# Sheet10.net
KiCad netlist of a schematic drawn in Altium Designer
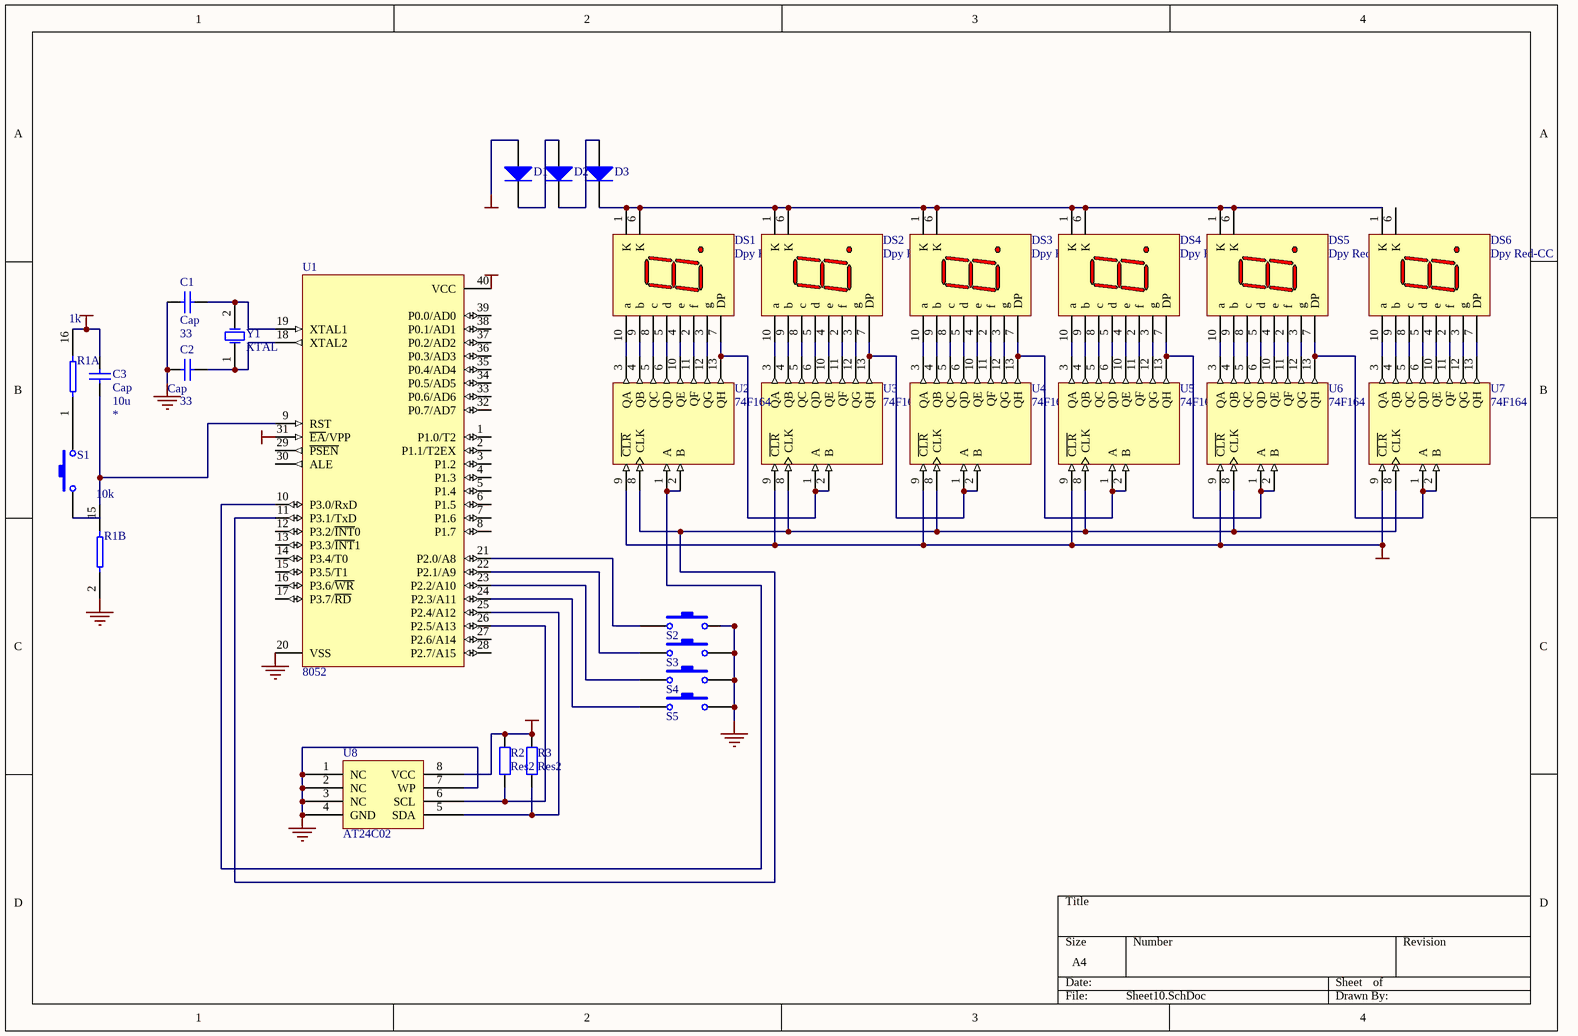
[diagram p0: Sheet10.SchDoc]

(export (version "E")
  (design (tool "Eeschema 10.0.6"))
  (components
    (comp (ref "C1")
      (value "Cap")
      (footprint "RAD-0.3")
      (description "Capacitor")
      (fields (field (name "ALTIUM_UNNAMED_1") "33") (field (name "PUBLISHER") "Altium Limited"))
      (libsource (lib "Miscellaneous Devices") (part "Cap"))
    )
    (comp (ref "C2")
      (value "Cap")
      (footprint "RAD-0.3")
      (description "Capacitor")
      (fields (field (name "ALTIUM_UNNAMED_1") "33") (field (name "PUBLISHER") "Altium Limited"))
      (libsource (lib "Miscellaneous Devices") (part "Cap"))
    )
    (comp (ref "C3")
      (value "Cap")
      (footprint "RAD-0.3")
      (description "Capacitor")
      (fields
        (field (name "ALTIUM_UNNAMED_1") "10u")
        (field (name "ALTIUM_UNNAMED_2") "*")
        (field (name "PUBLISHER") "Altium Limited")
      )
      (libsource (lib "Miscellaneous Devices") (part "Cap"))
    )
    (comp (ref "D1")
      (value "Diode BAS21")
      (footprint "SO-G3/C2.5")
      (description "Silicon Switching Diode for High-Speed, High-Voltage Switching")
      (fields (field (name "PUBLISHER") "Altium Limited"))
      (libsource (lib "Miscellaneous Devices") (part "Diode BAS21"))
    )
    (comp (ref "D2")
      (value "Diode BAS21")
      (footprint "SO-G3/C2.5")
      (description "Silicon Switching Diode for High-Speed, High-Voltage Switching")
      (fields (field (name "PUBLISHER") "Altium Limited"))
      (libsource (lib "Miscellaneous Devices") (part "Diode BAS21"))
    )
    (comp (ref "D3")
      (value "Diode BAS21")
      (footprint "SO-G3/C2.5")
      (description "Silicon Switching Diode for High-Speed, High-Voltage Switching")
      (fields (field (name "PUBLISHER") "Altium Limited"))
      (libsource (lib "Miscellaneous Devices") (part "Diode BAS21"))
    )
    (comp (ref "DS1")
      (value "Dpy Red-CC")
      (footprint "LEDDIP-10/C5.08RHD")
      (description "7.62 mm Black Surface HER 7-Segment Display: CC, RH DP")
      (fields (field (name "PUBLISHER") "Altium Limited"))
      (libsource (lib "Miscellaneous Devices") (part "Dpy Red-CC"))
    )
    (comp (ref "DS2")
      (value "Dpy Red-CC")
      (footprint "LEDDIP-10/C5.08RHD")
      (description "7.62 mm Black Surface HER 7-Segment Display: CC, RH DP")
      (fields (field (name "PUBLISHER") "Altium Limited"))
      (libsource (lib "Miscellaneous Devices") (part "Dpy Red-CC"))
    )
    (comp (ref "DS3")
      (value "Dpy Red-CC")
      (footprint "LEDDIP-10/C5.08RHD")
      (description "7.62 mm Black Surface HER 7-Segment Display: CC, RH DP")
      (fields (field (name "PUBLISHER") "Altium Limited"))
      (libsource (lib "Miscellaneous Devices") (part "Dpy Red-CC"))
    )
    (comp (ref "DS4")
      (value "Dpy Red-CC")
      (footprint "LEDDIP-10/C5.08RHD")
      (description "7.62 mm Black Surface HER 7-Segment Display: CC, RH DP")
      (fields (field (name "PUBLISHER") "Altium Limited"))
      (libsource (lib "Miscellaneous Devices") (part "Dpy Red-CC"))
    )
    (comp (ref "DS5")
      (value "Dpy Red-CC")
      (footprint "LEDDIP-10/C5.08RHD")
      (description "7.62 mm Black Surface HER 7-Segment Display: CC, RH DP")
      (fields (field (name "PUBLISHER") "Altium Limited"))
      (libsource (lib "Miscellaneous Devices") (part "Dpy Red-CC"))
    )
    (comp (ref "DS6")
      (value "Dpy Red-CC")
      (footprint "LEDDIP-10/C5.08RHD")
      (description "7.62 mm Black Surface HER 7-Segment Display: CC, RH DP")
      (fields (field (name "PUBLISHER") "Altium Limited"))
      (libsource (lib "Miscellaneous Devices") (part "Dpy Red-CC"))
    )
    (comp (ref "R1")
      (value "Res Pack2")
      (footprint "DIP-16")
      (description "Isolated Resistor Network - Parts")
      (fields (field (name "ALTIUM_UNNAMED_1") "1k") (field (name "PUBLISHER") "Altium Limited"))
      (libsource (lib "Miscellaneous Devices") (part "Res Pack2"))
    )
    (comp (ref "R2")
      (value "Res2")
      (footprint "AXIAL-0.4")
      (description "Resistor")
      (fields (field (name "PUBLISHER") "Altium Limited"))
      (libsource (lib "Miscellaneous Devices") (part "Res2"))
    )
    (comp (ref "R3")
      (value "Res2")
      (footprint "AXIAL-0.4")
      (description "Resistor")
      (fields (field (name "PUBLISHER") "Altium Limited"))
      (libsource (lib "Miscellaneous Devices") (part "Res2"))
    )
    (comp (ref "S1")
      (value "SW-PB")
      (footprint "SPST-2")
      (description "Switch")
      (fields (field (name "PUBLISHER") "Altium Limited"))
      (libsource (lib "Miscellaneous Devices") (part "SW-PB"))
    )
    (comp (ref "S2")
      (value "SW-PB")
      (footprint "SPST-2")
      (description "Switch")
      (fields (field (name "PUBLISHER") "Altium Limited"))
      (libsource (lib "Miscellaneous Devices") (part "SW-PB"))
    )
    (comp (ref "S3")
      (value "SW-PB")
      (footprint "SPST-2")
      (description "Switch")
      (fields (field (name "PUBLISHER") "Altium Limited"))
      (libsource (lib "Miscellaneous Devices") (part "SW-PB"))
    )
    (comp (ref "S4")
      (value "SW-PB")
      (footprint "SPST-2")
      (description "Switch")
      (fields (field (name "PUBLISHER") "Altium Limited"))
      (libsource (lib "Miscellaneous Devices") (part "SW-PB"))
    )
    (comp (ref "S5")
      (value "SW-PB")
      (footprint "SPST-2")
      (description "Switch")
      (fields (field (name "PUBLISHER") "Altium Limited"))
      (libsource (lib "Miscellaneous Devices") (part "SW-PB"))
    )
    (comp (ref "U1")
      (value "8052")
      (footprint "SOT129-1")
      (description "80C51 8-Bit Microcontroller Family: 128 B RAM, ROMless, 2.7 V-5.5 V, Low Power, High Speed")
      (fields (field (name "PUBLISHER") "Altium Limited"))
      (libsource (lib "Philips Microcontroller 8-Bit") (part "P80C31SBPN"))
    )
    (comp (ref "U2")
      (value "74F164")
      (footprint "DIP-14")
      (description "8-Bit Parallel-Out Serial Shift Register")
      (libsource (lib "74xx") (part "74F164"))
    )
    (comp (ref "U3")
      (value "74F164")
      (footprint "DIP-14")
      (description "8-Bit Parallel-Out Serial Shift Register")
      (libsource (lib "74xx") (part "74F164"))
    )
    (comp (ref "U4")
      (value "74F164")
      (footprint "DIP-14")
      (description "8-Bit Parallel-Out Serial Shift Register")
      (libsource (lib "74xx") (part "74F164"))
    )
    (comp (ref "U5")
      (value "74F164")
      (footprint "DIP-14")
      (description "8-Bit Parallel-Out Serial Shift Register")
      (libsource (lib "74xx") (part "74F164"))
    )
    (comp (ref "U6")
      (value "74F164")
      (footprint "DIP-14")
      (description "8-Bit Parallel-Out Serial Shift Register")
      (libsource (lib "74xx") (part "74F164"))
    )
    (comp (ref "U7")
      (value "74F164")
      (footprint "DIP-14")
      (description "8-Bit Parallel-Out Serial Shift Register")
      (libsource (lib "74xx") (part "74F164"))
    )
    (comp (ref "U8") (value "AT24C02") (libsource (lib "AT24C02") (part "Component_")))
    (comp (ref "Y1")
      (value "XTAL")
      (footprint "BCY-W2/D3.1")
      (description "Crystal Oscillator")
      (fields (field (name "PUBLISHER") "Altium Limited"))
      (libsource (lib "Miscellaneous Devices") (part "XTAL"))
    )
  )
  (nets
    (net (code "1") (name "+5") (class "Default")
      (node (ref "D1") (pin "1") (pinfunction "A_1") (pintype "passive"))
      (node (ref "R2") (pin "2") (pinfunction "2_2") (pintype "passive"))
      (node (ref "R3") (pin "2") (pinfunction "2_2") (pintype "passive"))
      (node (ref "U1") (pin "31") (pinfunction "~{EA}/VPP_31") (pintype "input"))
      (node (ref "U1") (pin "40") (pinfunction "VCC_40") (pintype "power_in"))
      (node (ref "U8") (pin "8") (pinfunction "VCC_8") (pintype "passive"))
    )
    (net (code "2") (name "+5v") (class "Default")
      (node (ref "C3") (pin "2") (pinfunction "2_2") (pintype "passive"))
      (node (ref "R1") (pin "16") (pinfunction "16_16") (pintype "passive"))
    )
    (net (code "3") (name "GND") (class "Default")
      (node (ref "C1") (pin "2") (pinfunction "2_2") (pintype "passive"))
      (node (ref "C2") (pin "2") (pinfunction "2_2") (pintype "passive"))
      (node (ref "R1") (pin "2") (pinfunction "2_2") (pintype "passive"))
      (node (ref "S2") (pin "2") (pinfunction "2_2") (pintype "passive"))
      (node (ref "S3") (pin "2") (pinfunction "2_2") (pintype "passive"))
      (node (ref "S4") (pin "2") (pinfunction "2_2") (pintype "passive"))
      (node (ref "S5") (pin "2") (pinfunction "2_2") (pintype "passive"))
      (node (ref "U1") (pin "20") (pinfunction "VSS_20") (pintype "power_in"))
      (node (ref "U2") (pin "7") (pinfunction "GND_7") (pintype "power_in"))
      (node (ref "U3") (pin "7") (pinfunction "GND_7") (pintype "power_in"))
      (node (ref "U4") (pin "7") (pinfunction "GND_7") (pintype "power_in"))
      (node (ref "U5") (pin "7") (pinfunction "GND_7") (pintype "power_in"))
      (node (ref "U6") (pin "7") (pinfunction "GND_7") (pintype "power_in"))
      (node (ref "U7") (pin "7") (pinfunction "GND_7") (pintype "power_in"))
      (node (ref "U8") (pin "1") (pinfunction "NC_1") (pintype "passive"))
      (node (ref "U8") (pin "2") (pinfunction "NC_2") (pintype "passive"))
      (node (ref "U8") (pin "3") (pinfunction "NC_3") (pintype "passive"))
      (node (ref "U8") (pin "4") (pinfunction "GND_4") (pintype "passive"))
      (node (ref "U8") (pin "7") (pinfunction "WP_7") (pintype "passive"))
    )
    (net (code "4") (name "Net-(D1-K)") (class "Default")
      (node (ref "D1") (pin "3") (pinfunction "K_3") (pintype "passive"))
      (node (ref "D2") (pin "1") (pinfunction "A_1") (pintype "passive"))
    )
    (net (code "5") (name "Net-(D2-K)") (class "Default")
      (node (ref "D2") (pin "3") (pinfunction "K_3") (pintype "passive"))
      (node (ref "D3") (pin "1") (pinfunction "A_1") (pintype "passive"))
    )
    (net (code "6") (name "Net-(D3-K)") (class "Default")
      (node (ref "D3") (pin "3") (pinfunction "K_3") (pintype "passive"))
      (node (ref "DS1") (pin "1") (pinfunction "K_1") (pintype "passive"))
      (node (ref "DS1") (pin "6") (pinfunction "K_6") (pintype "passive"))
      (node (ref "DS2") (pin "1") (pinfunction "K_1") (pintype "passive"))
      (node (ref "DS2") (pin "6") (pinfunction "K_6") (pintype "passive"))
      (node (ref "DS3") (pin "1") (pinfunction "K_1") (pintype "passive"))
      (node (ref "DS3") (pin "6") (pinfunction "K_6") (pintype "passive"))
      (node (ref "DS4") (pin "1") (pinfunction "K_1") (pintype "passive"))
      (node (ref "DS4") (pin "6") (pinfunction "K_6") (pintype "passive"))
      (node (ref "DS5") (pin "1") (pinfunction "K_1") (pintype "passive"))
      (node (ref "DS5") (pin "6") (pinfunction "K_6") (pintype "passive"))
      (node (ref "DS6") (pin "1") (pinfunction "K_1") (pintype "passive"))
    )
    (net (code "7") (name "Net-(DS1-DP)") (class "Default")
      (node (ref "DS1") (pin "7") (pinfunction "DP_7") (pintype "passive"))
      (node (ref "U2") (pin "13") (pinfunction "QH_13") (pintype "output"))
      (node (ref "U3") (pin "1") (pinfunction "A_1") (pintype "input"))
      (node (ref "U3") (pin "2") (pinfunction "B_2") (pintype "input"))
    )
    (net (code "8") (name "Net-(DS1-a)") (class "Default")
      (node (ref "DS1") (pin "10") (pinfunction "a_10") (pintype "passive"))
      (node (ref "U2") (pin "3") (pinfunction "QA_3") (pintype "output"))
    )
    (net (code "9") (name "Net-(DS1-b)") (class "Default")
      (node (ref "DS1") (pin "9") (pinfunction "b_9") (pintype "passive"))
      (node (ref "U2") (pin "4") (pinfunction "QB_4") (pintype "output"))
    )
    (net (code "10") (name "Net-(DS1-c)") (class "Default")
      (node (ref "DS1") (pin "8") (pinfunction "c_8") (pintype "passive"))
      (node (ref "U2") (pin "5") (pinfunction "QC_5") (pintype "output"))
    )
    (net (code "11") (name "Net-(DS1-d)") (class "Default")
      (node (ref "DS1") (pin "5") (pinfunction "d_5") (pintype "passive"))
      (node (ref "U2") (pin "6") (pinfunction "QD_6") (pintype "output"))
    )
    (net (code "12") (name "Net-(DS1-e)") (class "Default")
      (node (ref "DS1") (pin "4") (pinfunction "e_4") (pintype "passive"))
      (node (ref "U2") (pin "10") (pinfunction "QE_10") (pintype "output"))
    )
    (net (code "13") (name "Net-(DS1-f)") (class "Default")
      (node (ref "DS1") (pin "2") (pinfunction "f_2") (pintype "passive"))
      (node (ref "U2") (pin "11") (pinfunction "QF_11") (pintype "output"))
    )
    (net (code "14") (name "Net-(DS1-g)") (class "Default")
      (node (ref "DS1") (pin "3") (pinfunction "g_3") (pintype "passive"))
      (node (ref "U2") (pin "12") (pinfunction "QG_12") (pintype "output"))
    )
    (net (code "15") (name "Net-(DS2-DP)") (class "Default")
      (node (ref "DS2") (pin "7") (pinfunction "DP_7") (pintype "passive"))
      (node (ref "U3") (pin "13") (pinfunction "QH_13") (pintype "output"))
      (node (ref "U4") (pin "1") (pinfunction "A_1") (pintype "input"))
      (node (ref "U4") (pin "2") (pinfunction "B_2") (pintype "input"))
    )
    (net (code "16") (name "Net-(DS2-a)") (class "Default")
      (node (ref "DS2") (pin "10") (pinfunction "a_10") (pintype "passive"))
      (node (ref "U3") (pin "3") (pinfunction "QA_3") (pintype "output"))
    )
    (net (code "17") (name "Net-(DS2-b)") (class "Default")
      (node (ref "DS2") (pin "9") (pinfunction "b_9") (pintype "passive"))
      (node (ref "U3") (pin "4") (pinfunction "QB_4") (pintype "output"))
    )
    (net (code "18") (name "Net-(DS2-c)") (class "Default")
      (node (ref "DS2") (pin "8") (pinfunction "c_8") (pintype "passive"))
      (node (ref "U3") (pin "5") (pinfunction "QC_5") (pintype "output"))
    )
    (net (code "19") (name "Net-(DS2-d)") (class "Default")
      (node (ref "DS2") (pin "5") (pinfunction "d_5") (pintype "passive"))
      (node (ref "U3") (pin "6") (pinfunction "QD_6") (pintype "output"))
    )
    (net (code "20") (name "Net-(DS2-e)") (class "Default")
      (node (ref "DS2") (pin "4") (pinfunction "e_4") (pintype "passive"))
      (node (ref "U3") (pin "10") (pinfunction "QE_10") (pintype "output"))
    )
    (net (code "21") (name "Net-(DS2-f)") (class "Default")
      (node (ref "DS2") (pin "2") (pinfunction "f_2") (pintype "passive"))
      (node (ref "U3") (pin "11") (pinfunction "QF_11") (pintype "output"))
    )
    (net (code "22") (name "Net-(DS2-g)") (class "Default")
      (node (ref "DS2") (pin "3") (pinfunction "g_3") (pintype "passive"))
      (node (ref "U3") (pin "12") (pinfunction "QG_12") (pintype "output"))
    )
    (net (code "23") (name "Net-(DS3-DP)") (class "Default")
      (node (ref "DS3") (pin "7") (pinfunction "DP_7") (pintype "passive"))
      (node (ref "U4") (pin "13") (pinfunction "QH_13") (pintype "output"))
      (node (ref "U5") (pin "1") (pinfunction "A_1") (pintype "input"))
      (node (ref "U5") (pin "2") (pinfunction "B_2") (pintype "input"))
    )
    (net (code "24") (name "Net-(DS3-a)") (class "Default")
      (node (ref "DS3") (pin "10") (pinfunction "a_10") (pintype "passive"))
      (node (ref "U4") (pin "3") (pinfunction "QA_3") (pintype "output"))
    )
    (net (code "25") (name "Net-(DS3-b)") (class "Default")
      (node (ref "DS3") (pin "9") (pinfunction "b_9") (pintype "passive"))
      (node (ref "U4") (pin "4") (pinfunction "QB_4") (pintype "output"))
    )
    (net (code "26") (name "Net-(DS3-c)") (class "Default")
      (node (ref "DS3") (pin "8") (pinfunction "c_8") (pintype "passive"))
      (node (ref "U4") (pin "5") (pinfunction "QC_5") (pintype "output"))
    )
    (net (code "27") (name "Net-(DS3-d)") (class "Default")
      (node (ref "DS3") (pin "5") (pinfunction "d_5") (pintype "passive"))
      (node (ref "U4") (pin "6") (pinfunction "QD_6") (pintype "output"))
    )
    (net (code "28") (name "Net-(DS3-e)") (class "Default")
      (node (ref "DS3") (pin "4") (pinfunction "e_4") (pintype "passive"))
      (node (ref "U4") (pin "10") (pinfunction "QE_10") (pintype "output"))
    )
    (net (code "29") (name "Net-(DS3-f)") (class "Default")
      (node (ref "DS3") (pin "2") (pinfunction "f_2") (pintype "passive"))
      (node (ref "U4") (pin "11") (pinfunction "QF_11") (pintype "output"))
    )
    (net (code "30") (name "Net-(DS3-g)") (class "Default")
      (node (ref "DS3") (pin "3") (pinfunction "g_3") (pintype "passive"))
      (node (ref "U4") (pin "12") (pinfunction "QG_12") (pintype "output"))
    )
    (net (code "31") (name "Net-(DS4-DP)") (class "Default")
      (node (ref "DS4") (pin "7") (pinfunction "DP_7") (pintype "passive"))
      (node (ref "U5") (pin "13") (pinfunction "QH_13") (pintype "output"))
      (node (ref "U6") (pin "1") (pinfunction "A_1") (pintype "input"))
      (node (ref "U6") (pin "2") (pinfunction "B_2") (pintype "input"))
    )
    (net (code "32") (name "Net-(DS4-a)") (class "Default")
      (node (ref "DS4") (pin "10") (pinfunction "a_10") (pintype "passive"))
      (node (ref "U5") (pin "3") (pinfunction "QA_3") (pintype "output"))
    )
    (net (code "33") (name "Net-(DS4-b)") (class "Default")
      (node (ref "DS4") (pin "9") (pinfunction "b_9") (pintype "passive"))
      (node (ref "U5") (pin "4") (pinfunction "QB_4") (pintype "output"))
    )
    (net (code "34") (name "Net-(DS4-c)") (class "Default")
      (node (ref "DS4") (pin "8") (pinfunction "c_8") (pintype "passive"))
      (node (ref "U5") (pin "5") (pinfunction "QC_5") (pintype "output"))
    )
    (net (code "35") (name "Net-(DS4-d)") (class "Default")
      (node (ref "DS4") (pin "5") (pinfunction "d_5") (pintype "passive"))
      (node (ref "U5") (pin "6") (pinfunction "QD_6") (pintype "output"))
    )
    (net (code "36") (name "Net-(DS4-e)") (class "Default")
      (node (ref "DS4") (pin "4") (pinfunction "e_4") (pintype "passive"))
      (node (ref "U5") (pin "10") (pinfunction "QE_10") (pintype "output"))
    )
    (net (code "37") (name "Net-(DS4-f)") (class "Default")
      (node (ref "DS4") (pin "2") (pinfunction "f_2") (pintype "passive"))
      (node (ref "U5") (pin "11") (pinfunction "QF_11") (pintype "output"))
    )
    (net (code "38") (name "Net-(DS4-g)") (class "Default")
      (node (ref "DS4") (pin "3") (pinfunction "g_3") (pintype "passive"))
      (node (ref "U5") (pin "12") (pinfunction "QG_12") (pintype "output"))
    )
    (net (code "39") (name "Net-(DS5-DP)") (class "Default")
      (node (ref "DS5") (pin "7") (pinfunction "DP_7") (pintype "passive"))
      (node (ref "U6") (pin "13") (pinfunction "QH_13") (pintype "output"))
      (node (ref "U7") (pin "1") (pinfunction "A_1") (pintype "input"))
      (node (ref "U7") (pin "2") (pinfunction "B_2") (pintype "input"))
    )
    (net (code "40") (name "Net-(DS5-a)") (class "Default")
      (node (ref "DS5") (pin "10") (pinfunction "a_10") (pintype "passive"))
      (node (ref "U6") (pin "3") (pinfunction "QA_3") (pintype "output"))
    )
    (net (code "41") (name "Net-(DS5-b)") (class "Default")
      (node (ref "DS5") (pin "9") (pinfunction "b_9") (pintype "passive"))
      (node (ref "U6") (pin "4") (pinfunction "QB_4") (pintype "output"))
    )
    (net (code "42") (name "Net-(DS5-c)") (class "Default")
      (node (ref "DS5") (pin "8") (pinfunction "c_8") (pintype "passive"))
      (node (ref "U6") (pin "5") (pinfunction "QC_5") (pintype "output"))
    )
    (net (code "43") (name "Net-(DS5-d)") (class "Default")
      (node (ref "DS5") (pin "5") (pinfunction "d_5") (pintype "passive"))
      (node (ref "U6") (pin "6") (pinfunction "QD_6") (pintype "output"))
    )
    (net (code "44") (name "Net-(DS5-e)") (class "Default")
      (node (ref "DS5") (pin "4") (pinfunction "e_4") (pintype "passive"))
      (node (ref "U6") (pin "10") (pinfunction "QE_10") (pintype "output"))
    )
    (net (code "45") (name "Net-(DS5-f)") (class "Default")
      (node (ref "DS5") (pin "2") (pinfunction "f_2") (pintype "passive"))
      (node (ref "U6") (pin "11") (pinfunction "QF_11") (pintype "output"))
    )
    (net (code "46") (name "Net-(DS5-g)") (class "Default")
      (node (ref "DS5") (pin "3") (pinfunction "g_3") (pintype "passive"))
      (node (ref "U6") (pin "12") (pinfunction "QG_12") (pintype "output"))
    )
    (net (code "47") (name "Net-(DS6-DP)") (class "Default")
      (node (ref "DS6") (pin "7") (pinfunction "DP_7") (pintype "passive"))
      (node (ref "U7") (pin "13") (pinfunction "QH_13") (pintype "output"))
    )
    (net (code "48") (name "Net-(DS6-a)") (class "Default")
      (node (ref "DS6") (pin "10") (pinfunction "a_10") (pintype "passive"))
      (node (ref "U7") (pin "3") (pinfunction "QA_3") (pintype "output"))
    )
    (net (code "49") (name "Net-(DS6-b)") (class "Default")
      (node (ref "DS6") (pin "9") (pinfunction "b_9") (pintype "passive"))
      (node (ref "U7") (pin "4") (pinfunction "QB_4") (pintype "output"))
    )
    (net (code "50") (name "Net-(DS6-c)") (class "Default")
      (node (ref "DS6") (pin "8") (pinfunction "c_8") (pintype "passive"))
      (node (ref "U7") (pin "5") (pinfunction "QC_5") (pintype "output"))
    )
    (net (code "51") (name "Net-(DS6-d)") (class "Default")
      (node (ref "DS6") (pin "5") (pinfunction "d_5") (pintype "passive"))
      (node (ref "U7") (pin "6") (pinfunction "QD_6") (pintype "output"))
    )
    (net (code "52") (name "Net-(DS6-e)") (class "Default")
      (node (ref "DS6") (pin "4") (pinfunction "e_4") (pintype "passive"))
      (node (ref "U7") (pin "10") (pinfunction "QE_10") (pintype "output"))
    )
    (net (code "53") (name "Net-(DS6-f)") (class "Default")
      (node (ref "DS6") (pin "2") (pinfunction "f_2") (pintype "passive"))
      (node (ref "U7") (pin "11") (pinfunction "QF_11") (pintype "output"))
    )
    (net (code "54") (name "Net-(DS6-g)") (class "Default")
      (node (ref "DS6") (pin "3") (pinfunction "g_3") (pintype "passive"))
      (node (ref "U7") (pin "12") (pinfunction "QG_12") (pintype "output"))
    )
    (net (code "55") (name "Net-(R1-Pad1)") (class "Default")
      (node (ref "R1") (pin "1") (pinfunction "1_1") (pintype "passive"))
      (node (ref "S1") (pin "2") (pinfunction "2_2") (pintype "passive"))
    )
    (net (code "56") (name "Net-(U1-P2.0{slash}A8)") (class "Default")
      (node (ref "S2") (pin "1") (pinfunction "1_1") (pintype "passive"))
      (node (ref "U1") (pin "21") (pinfunction "P2.0/A8_21") (pintype "bidirectional"))
    )
    (net (code "57") (name "Net-(U1-P2.1{slash}A9)") (class "Default")
      (node (ref "S3") (pin "1") (pinfunction "1_1") (pintype "passive"))
      (node (ref "U1") (pin "22") (pinfunction "P2.1/A9_22") (pintype "bidirectional"))
    )
    (net (code "58") (name "Net-(U1-P2.2{slash}A10)") (class "Default")
      (node (ref "S4") (pin "1") (pinfunction "1_1") (pintype "passive"))
      (node (ref "U1") (pin "23") (pinfunction "P2.2/A10_23") (pintype "bidirectional"))
    )
    (net (code "59") (name "Net-(U1-P2.3{slash}A11)") (class "Default")
      (node (ref "S5") (pin "1") (pinfunction "1_1") (pintype "passive"))
      (node (ref "U1") (pin "24") (pinfunction "P2.3/A11_24") (pintype "bidirectional"))
    )
    (net (code "60") (name "Net-(U1-P2.4{slash}A12)") (class "Default")
      (node (ref "R3") (pin "1") (pinfunction "1_1") (pintype "passive"))
      (node (ref "U1") (pin "25") (pinfunction "P2.4/A12_25") (pintype "bidirectional"))
      (node (ref "U8") (pin "5") (pinfunction "SDA_5") (pintype "passive"))
    )
    (net (code "61") (name "Net-(U1-P2.5{slash}A13)") (class "Default")
      (node (ref "R2") (pin "1") (pinfunction "1_1") (pintype "passive"))
      (node (ref "U1") (pin "26") (pinfunction "P2.5/A13_26") (pintype "bidirectional"))
      (node (ref "U8") (pin "6") (pinfunction "SCL_6") (pintype "passive"))
    )
    (net (code "62") (name "Net-(U1-P3.0{slash}RxD)") (class "Default")
      (node (ref "U1") (pin "10") (pinfunction "P3.0/RxD_10") (pintype "bidirectional"))
      (node (ref "U2") (pin "1") (pinfunction "A_1") (pintype "input"))
      (node (ref "U2") (pin "2") (pinfunction "B_2") (pintype "input"))
    )
    (net (code "63") (name "Net-(U1-P3.1{slash}TxD)") (class "Default")
      (node (ref "U1") (pin "11") (pinfunction "P3.1/TxD_11") (pintype "bidirectional"))
      (node (ref "U2") (pin "8") (pinfunction "CLK_8") (pintype "input"))
      (node (ref "U3") (pin "8") (pinfunction "CLK_8") (pintype "input"))
      (node (ref "U4") (pin "8") (pinfunction "CLK_8") (pintype "input"))
      (node (ref "U5") (pin "8") (pinfunction "CLK_8") (pintype "input"))
      (node (ref "U6") (pin "8") (pinfunction "CLK_8") (pintype "input"))
      (node (ref "U7") (pin "8") (pinfunction "CLK_8") (pintype "input"))
    )
    (net (code "64") (name "Net-(U1-RST)") (class "Default")
      (node (ref "C3") (pin "1") (pinfunction "1_1") (pintype "passive"))
      (node (ref "R1") (pin "15") (pinfunction "15_15") (pintype "passive"))
      (node (ref "U1") (pin "9") (pinfunction "RST_9") (pintype "input"))
    )
    (net (code "65") (name "Net-(U1-XTAL1)") (class "Default")
      (node (ref "C1") (pin "1") (pinfunction "1_1") (pintype "passive"))
      (node (ref "U1") (pin "19") (pinfunction "XTAL1_19") (pintype "input"))
      (node (ref "Y1") (pin "2") (pinfunction "OSC2_2") (pintype "passive"))
    )
    (net (code "66") (name "Net-(U1-XTAL2)") (class "Default")
      (node (ref "C2") (pin "1") (pinfunction "1_1") (pintype "passive"))
      (node (ref "U1") (pin "18") (pinfunction "XTAL2_18") (pintype "output"))
      (node (ref "Y1") (pin "1") (pinfunction "OSC1_1") (pintype "passive"))
    )
    (net (code "67") (name "VCC") (class "Default")
      (node (ref "U2") (pin "14") (pinfunction "VCC_14") (pintype "power_in"))
      (node (ref "U2") (pin "9") (pinfunction "~{CLR}_9") (pintype "input"))
      (node (ref "U3") (pin "14") (pinfunction "VCC_14") (pintype "power_in"))
      (node (ref "U3") (pin "9") (pinfunction "~{CLR}_9") (pintype "input"))
      (node (ref "U4") (pin "14") (pinfunction "VCC_14") (pintype "power_in"))
      (node (ref "U4") (pin "9") (pinfunction "~{CLR}_9") (pintype "input"))
      (node (ref "U5") (pin "14") (pinfunction "VCC_14") (pintype "power_in"))
      (node (ref "U5") (pin "9") (pinfunction "~{CLR}_9") (pintype "input"))
      (node (ref "U6") (pin "14") (pinfunction "VCC_14") (pintype "power_in"))
      (node (ref "U6") (pin "9") (pinfunction "~{CLR}_9") (pintype "input"))
      (node (ref "U7") (pin "14") (pinfunction "VCC_14") (pintype "power_in"))
      (node (ref "U7") (pin "9") (pinfunction "~{CLR}_9") (pintype "input"))
    )
    (net (code "68") (name "unconnected-(DS6-K-Pad6)") (class "Default")
      (node (ref "DS6") (pin "6") (pinfunction "K_6") (pintype "passive"))
    )
    (net (code "69") (name "unconnected-(S1-Pad1)") (class "Default")
      (node (ref "S1") (pin "1") (pinfunction "1_1") (pintype "passive"))
    )
    (net (code "70") (name "unconnected-(U1-ALE-Pad30)") (class "Default")
      (node (ref "U1") (pin "30") (pinfunction "ALE_30") (pintype "output"))
    )
    (net (code "71") (name "unconnected-(U1-P0.0{slash}AD0-Pad39)") (class "Default")
      (node (ref "U1") (pin "39") (pinfunction "P0.0/AD0_39") (pintype "bidirectional"))
    )
    (net (code "72") (name "unconnected-(U1-P0.1{slash}AD1-Pad38)") (class "Default")
      (node (ref "U1") (pin "38") (pinfunction "P0.1/AD1_38") (pintype "bidirectional"))
    )
    (net (code "73") (name "unconnected-(U1-P0.2{slash}AD2-Pad37)") (class "Default")
      (node (ref "U1") (pin "37") (pinfunction "P0.2/AD2_37") (pintype "bidirectional"))
    )
    (net (code "74") (name "unconnected-(U1-P0.3{slash}AD3-Pad36)") (class "Default")
      (node (ref "U1") (pin "36") (pinfunction "P0.3/AD3_36") (pintype "bidirectional"))
    )
    (net (code "75") (name "unconnected-(U1-P0.4{slash}AD4-Pad35)") (class "Default")
      (node (ref "U1") (pin "35") (pinfunction "P0.4/AD4_35") (pintype "bidirectional"))
    )
    (net (code "76") (name "unconnected-(U1-P0.5{slash}AD5-Pad34)") (class "Default")
      (node (ref "U1") (pin "34") (pinfunction "P0.5/AD5_34") (pintype "bidirectional"))
    )
    (net (code "77") (name "unconnected-(U1-P0.6{slash}AD6-Pad33)") (class "Default")
      (node (ref "U1") (pin "33") (pinfunction "P0.6/AD6_33") (pintype "bidirectional"))
    )
    (net (code "78") (name "unconnected-(U1-P0.7{slash}AD7-Pad32)") (class "Default")
      (node (ref "U1") (pin "32") (pinfunction "P0.7/AD7_32") (pintype "bidirectional"))
    )
    (net (code "79") (name "unconnected-(U1-P1.0{slash}T2-Pad1)") (class "Default")
      (node (ref "U1") (pin "1") (pinfunction "P1.0/T2_1") (pintype "bidirectional"))
    )
    (net (code "80") (name "unconnected-(U1-P1.1{slash}T2EX-Pad2)") (class "Default")
      (node (ref "U1") (pin "2") (pinfunction "P1.1/T2EX_2") (pintype "bidirectional"))
    )
    (net (code "81") (name "unconnected-(U1-P1.2-Pad3)") (class "Default")
      (node (ref "U1") (pin "3") (pinfunction "P1.2_3") (pintype "bidirectional"))
    )
    (net (code "82") (name "unconnected-(U1-P1.3-Pad4)") (class "Default")
      (node (ref "U1") (pin "4") (pinfunction "P1.3_4") (pintype "bidirectional"))
    )
    (net (code "83") (name "unconnected-(U1-P1.4-Pad5)") (class "Default")
      (node (ref "U1") (pin "5") (pinfunction "P1.4_5") (pintype "bidirectional"))
    )
    (net (code "84") (name "unconnected-(U1-P1.5-Pad6)") (class "Default")
      (node (ref "U1") (pin "6") (pinfunction "P1.5_6") (pintype "bidirectional"))
    )
    (net (code "85") (name "unconnected-(U1-P1.6-Pad7)") (class "Default")
      (node (ref "U1") (pin "7") (pinfunction "P1.6_7") (pintype "bidirectional"))
    )
    (net (code "86") (name "unconnected-(U1-P1.7-Pad8)") (class "Default")
      (node (ref "U1") (pin "8") (pinfunction "P1.7_8") (pintype "bidirectional"))
    )
    (net (code "87") (name "unconnected-(U1-P2.6{slash}A14-Pad27)") (class "Default")
      (node (ref "U1") (pin "27") (pinfunction "P2.6/A14_27") (pintype "bidirectional"))
    )
    (net (code "88") (name "unconnected-(U1-P2.7{slash}A15-Pad28)") (class "Default")
      (node (ref "U1") (pin "28") (pinfunction "P2.7/A15_28") (pintype "bidirectional"))
    )
    (net (code "89") (name "unconnected-(U1-P3.2{slash}~{INT}0-Pad12)") (class "Default")
      (node (ref "U1") (pin "12") (pinfunction "P3.2/~{INT}0_12") (pintype "bidirectional"))
    )
    (net (code "90") (name "unconnected-(U1-P3.3{slash}~{INT}1-Pad13)") (class "Default")
      (node (ref "U1") (pin "13") (pinfunction "P3.3/~{INT}1_13") (pintype "bidirectional"))
    )
    (net (code "91") (name "unconnected-(U1-P3.4{slash}T0-Pad14)") (class "Default")
      (node (ref "U1") (pin "14") (pinfunction "P3.4/T0_14") (pintype "bidirectional"))
    )
    (net (code "92") (name "unconnected-(U1-P3.5{slash}T1-Pad15)") (class "Default")
      (node (ref "U1") (pin "15") (pinfunction "P3.5/T1_15") (pintype "bidirectional"))
    )
    (net (code "93") (name "unconnected-(U1-P3.6{slash}~{WR}-Pad16)") (class "Default")
      (node (ref "U1") (pin "16") (pinfunction "P3.6/~{WR}_16") (pintype "bidirectional"))
    )
    (net (code "94") (name "unconnected-(U1-P3.7{slash}~{RD}-Pad17)") (class "Default")
      (node (ref "U1") (pin "17") (pinfunction "P3.7/~{RD}_17") (pintype "bidirectional"))
    )
    (net (code "95") (name "unconnected-(U1-~{PSEN}-Pad29)") (class "Default")
      (node (ref "U1") (pin "29") (pinfunction "~{PSEN}_29") (pintype "output"))
    )
  )
)
